# Sheet1.net
KiCad netlist of a schematic drawn in Altium Designer
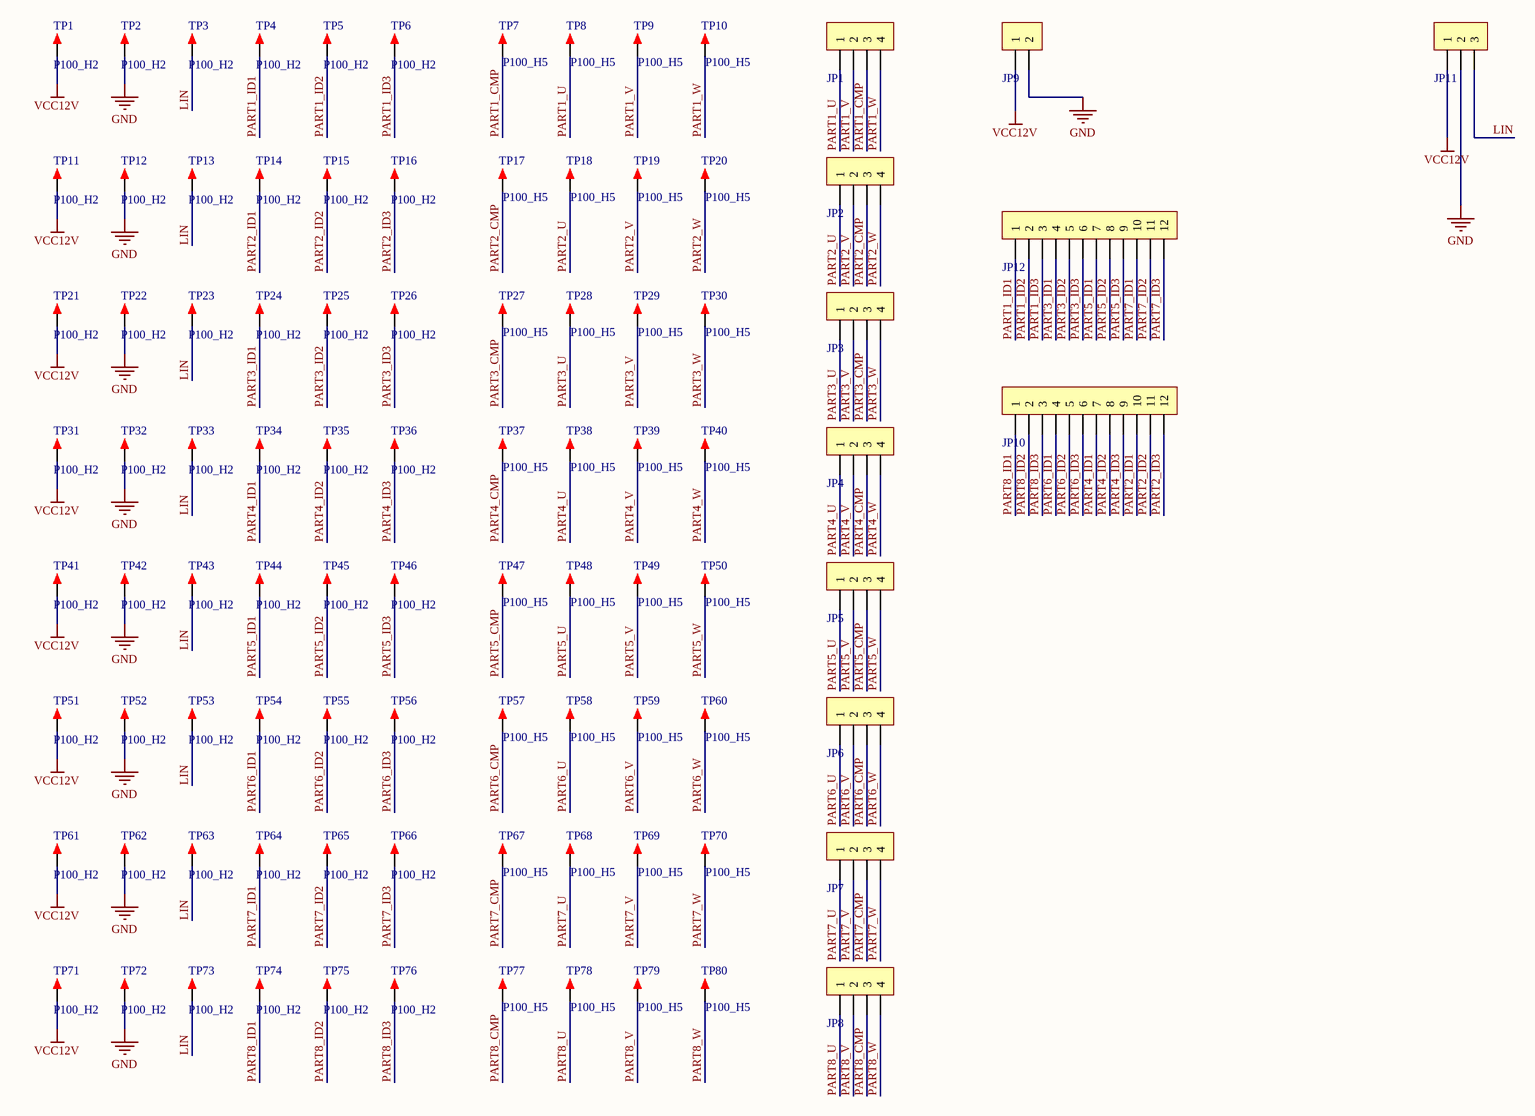
[diagram p0: Sheet1.SchDoc]

(export (version "E")
  (design (tool "Eeschema 10.0.6"))
  (components
    (comp (ref "JP1")
      (value "HDR-1X4")
      (footprint "XH2.54-LS-4P")
      (description "4P接插件")
      (fields (field (name "版权归属") "源创客"))
      (libsource (lib "Connector-PinHeader") (part "Header 4"))
    )
    (comp (ref "JP2")
      (value "HDR-1X4")
      (footprint "XH2.54-LS-4P")
      (description "4P接插件")
      (fields (field (name "版权归属") "源创客"))
      (libsource (lib "Connector-PinHeader") (part "Header 4"))
    )
    (comp (ref "JP3")
      (value "HDR-1X4")
      (footprint "XH2.54-LS-4P")
      (description "4P接插件")
      (fields (field (name "版权归属") "源创客"))
      (libsource (lib "Connector-PinHeader") (part "Header 4"))
    )
    (comp (ref "JP4")
      (value "HDR-1X4")
      (footprint "XH2.54-LS-4P")
      (description "4P接插件")
      (fields (field (name "版权归属") "源创客"))
      (libsource (lib "Connector-PinHeader") (part "Header 4"))
    )
    (comp (ref "JP5")
      (value "HDR-1X4")
      (footprint "XH2.54-LS-4P")
      (description "4P接插件")
      (fields (field (name "版权归属") "源创客"))
      (libsource (lib "Connector-PinHeader") (part "Header 4"))
    )
    (comp (ref "JP6")
      (value "HDR-1X4")
      (footprint "XH2.54-LS-4P")
      (description "4P接插件")
      (fields (field (name "版权归属") "源创客"))
      (libsource (lib "Connector-PinHeader") (part "Header 4"))
    )
    (comp (ref "JP7")
      (value "HDR-1X4")
      (footprint "XH2.54-LS-4P")
      (description "4P接插件")
      (fields (field (name "版权归属") "源创客"))
      (libsource (lib "Connector-PinHeader") (part "Header 4"))
    )
    (comp (ref "JP8")
      (value "HDR-1X4")
      (footprint "XH2.54-LS-4P")
      (description "4P接插件")
      (fields (field (name "版权归属") "源创客"))
      (libsource (lib "Connector-PinHeader") (part "Header 4"))
    )
    (comp (ref "JP9")
      (value "HDR-1X2")
      (footprint "DC-005P")
      (description "2P接插件")
      (fields (field (name "版权归属") "源创客"))
      (libsource (lib "Connector-PinHeader") (part "Header 2"))
    )
    (comp (ref "JP10")
      (value "HDR-1X12")
      (footprint "MX 1.25-WS-12P")
      (description "12P接插件")
      (fields (field (name "版权归属") "源创客"))
      (libsource (lib "Connector-PinHeader") (part "Header 12"))
    )
    (comp (ref "JP11")
      (value "HDR-1X3")
      (footprint "XH2.54-WS-3P")
      (description "3P接插件")
      (fields (field (name "版权归属") "源创客"))
      (libsource (lib "Connector-PinHeader") (part "Header 3"))
    )
    (comp (ref "JP12")
      (value "HDR-1X12")
      (footprint "MX 1.25-WS-12P")
      (description "12P接插件")
      (fields (field (name "版权归属") "源创客"))
      (libsource (lib "Connector-PinHeader") (part "Header 12"))
    )
    (comp (ref "TP1")
      (value "P100_H2")
      (footprint "P100_H2")
      (description "测试点")
      (fields (field (name "版权归属") "源创客"))
      (libsource (lib "Hole") (part "TEST"))
    )
    (comp (ref "TP2")
      (value "P100_H2")
      (footprint "P100_H2")
      (description "测试点")
      (fields (field (name "版权归属") "源创客"))
      (libsource (lib "Hole") (part "TEST"))
    )
    (comp (ref "TP3")
      (value "P100_H2")
      (footprint "P100_H2")
      (description "测试点")
      (fields (field (name "版权归属") "源创客"))
      (libsource (lib "Hole") (part "TEST"))
    )
    (comp (ref "TP4")
      (value "P100_H2")
      (footprint "P100_H2")
      (description "测试点")
      (fields (field (name "版权归属") "源创客"))
      (libsource (lib "Hole") (part "TEST"))
    )
    (comp (ref "TP5")
      (value "P100_H2")
      (footprint "P100_H2")
      (description "测试点")
      (fields (field (name "版权归属") "源创客"))
      (libsource (lib "Hole") (part "TEST"))
    )
    (comp (ref "TP6")
      (value "P100_H2")
      (footprint "P100_H2")
      (description "测试点")
      (fields (field (name "版权归属") "源创客"))
      (libsource (lib "Hole") (part "TEST"))
    )
    (comp (ref "TP7")
      (value "P100_H5")
      (footprint "P100_H5")
      (description "测试点")
      (fields (field (name "版权归属") "源创客"))
      (libsource (lib "Hole") (part "TEST"))
    )
    (comp (ref "TP8")
      (value "P100_H5")
      (footprint "P100_H5")
      (description "测试点")
      (fields (field (name "版权归属") "源创客"))
      (libsource (lib "Hole") (part "TEST"))
    )
    (comp (ref "TP9")
      (value "P100_H5")
      (footprint "P100_H5")
      (description "测试点")
      (fields (field (name "版权归属") "源创客"))
      (libsource (lib "Hole") (part "TEST"))
    )
    (comp (ref "TP10")
      (value "P100_H5")
      (footprint "P100_H5")
      (description "测试点")
      (fields (field (name "版权归属") "源创客"))
      (libsource (lib "Hole") (part "TEST"))
    )
    (comp (ref "TP11")
      (value "P100_H2")
      (footprint "P100_H2")
      (description "测试点")
      (fields (field (name "版权归属") "源创客"))
      (libsource (lib "Hole") (part "TEST"))
    )
    (comp (ref "TP12")
      (value "P100_H2")
      (footprint "P100_H2")
      (description "测试点")
      (fields (field (name "版权归属") "源创客"))
      (libsource (lib "Hole") (part "TEST"))
    )
    (comp (ref "TP13")
      (value "P100_H2")
      (footprint "P100_H2")
      (description "测试点")
      (fields (field (name "版权归属") "源创客"))
      (libsource (lib "Hole") (part "TEST"))
    )
    (comp (ref "TP14")
      (value "P100_H2")
      (footprint "P100_H2")
      (description "测试点")
      (fields (field (name "版权归属") "源创客"))
      (libsource (lib "Hole") (part "TEST"))
    )
    (comp (ref "TP15")
      (value "P100_H2")
      (footprint "P100_H2")
      (description "测试点")
      (fields (field (name "版权归属") "源创客"))
      (libsource (lib "Hole") (part "TEST"))
    )
    (comp (ref "TP16")
      (value "P100_H2")
      (footprint "P100_H2")
      (description "测试点")
      (fields (field (name "版权归属") "源创客"))
      (libsource (lib "Hole") (part "TEST"))
    )
    (comp (ref "TP17")
      (value "P100_H5")
      (footprint "P100_H5")
      (description "测试点")
      (fields (field (name "版权归属") "源创客"))
      (libsource (lib "Hole") (part "TEST"))
    )
    (comp (ref "TP18")
      (value "P100_H5")
      (footprint "P100_H5")
      (description "测试点")
      (fields (field (name "版权归属") "源创客"))
      (libsource (lib "Hole") (part "TEST"))
    )
    (comp (ref "TP19")
      (value "P100_H5")
      (footprint "P100_H5")
      (description "测试点")
      (fields (field (name "版权归属") "源创客"))
      (libsource (lib "Hole") (part "TEST"))
    )
    (comp (ref "TP20")
      (value "P100_H5")
      (footprint "P100_H5")
      (description "测试点")
      (fields (field (name "版权归属") "源创客"))
      (libsource (lib "Hole") (part "TEST"))
    )
    (comp (ref "TP21")
      (value "P100_H2")
      (footprint "P100_H2")
      (description "测试点")
      (fields (field (name "版权归属") "源创客"))
      (libsource (lib "Hole") (part "TEST"))
    )
    (comp (ref "TP22")
      (value "P100_H2")
      (footprint "P100_H2")
      (description "测试点")
      (fields (field (name "版权归属") "源创客"))
      (libsource (lib "Hole") (part "TEST"))
    )
    (comp (ref "TP23")
      (value "P100_H2")
      (footprint "P100_H2")
      (description "测试点")
      (fields (field (name "版权归属") "源创客"))
      (libsource (lib "Hole") (part "TEST"))
    )
    (comp (ref "TP24")
      (value "P100_H2")
      (footprint "P100_H2")
      (description "测试点")
      (fields (field (name "版权归属") "源创客"))
      (libsource (lib "Hole") (part "TEST"))
    )
    (comp (ref "TP25")
      (value "P100_H2")
      (footprint "P100_H2")
      (description "测试点")
      (fields (field (name "版权归属") "源创客"))
      (libsource (lib "Hole") (part "TEST"))
    )
    (comp (ref "TP26")
      (value "P100_H2")
      (footprint "P100_H2")
      (description "测试点")
      (fields (field (name "版权归属") "源创客"))
      (libsource (lib "Hole") (part "TEST"))
    )
    (comp (ref "TP27")
      (value "P100_H5")
      (footprint "P100_H5")
      (description "测试点")
      (fields (field (name "版权归属") "源创客"))
      (libsource (lib "Hole") (part "TEST"))
    )
    (comp (ref "TP28")
      (value "P100_H5")
      (footprint "P100_H5")
      (description "测试点")
      (fields (field (name "版权归属") "源创客"))
      (libsource (lib "Hole") (part "TEST"))
    )
    (comp (ref "TP29")
      (value "P100_H5")
      (footprint "P100_H5")
      (description "测试点")
      (fields (field (name "版权归属") "源创客"))
      (libsource (lib "Hole") (part "TEST"))
    )
    (comp (ref "TP30")
      (value "P100_H5")
      (footprint "P100_H5")
      (description "测试点")
      (fields (field (name "版权归属") "源创客"))
      (libsource (lib "Hole") (part "TEST"))
    )
    (comp (ref "TP31")
      (value "P100_H2")
      (footprint "P100_H2")
      (description "测试点")
      (fields (field (name "版权归属") "源创客"))
      (libsource (lib "Hole") (part "TEST"))
    )
    (comp (ref "TP32")
      (value "P100_H2")
      (footprint "P100_H2")
      (description "测试点")
      (fields (field (name "版权归属") "源创客"))
      (libsource (lib "Hole") (part "TEST"))
    )
    (comp (ref "TP33")
      (value "P100_H2")
      (footprint "P100_H2")
      (description "测试点")
      (fields (field (name "版权归属") "源创客"))
      (libsource (lib "Hole") (part "TEST"))
    )
    (comp (ref "TP34")
      (value "P100_H2")
      (footprint "P100_H2")
      (description "测试点")
      (fields (field (name "版权归属") "源创客"))
      (libsource (lib "Hole") (part "TEST"))
    )
    (comp (ref "TP35")
      (value "P100_H2")
      (footprint "P100_H2")
      (description "测试点")
      (fields (field (name "版权归属") "源创客"))
      (libsource (lib "Hole") (part "TEST"))
    )
    (comp (ref "TP36")
      (value "P100_H2")
      (footprint "P100_H2")
      (description "测试点")
      (fields (field (name "版权归属") "源创客"))
      (libsource (lib "Hole") (part "TEST"))
    )
    (comp (ref "TP37")
      (value "P100_H5")
      (footprint "P100_H5")
      (description "测试点")
      (fields (field (name "版权归属") "源创客"))
      (libsource (lib "Hole") (part "TEST"))
    )
    (comp (ref "TP38")
      (value "P100_H5")
      (footprint "P100_H5")
      (description "测试点")
      (fields (field (name "版权归属") "源创客"))
      (libsource (lib "Hole") (part "TEST"))
    )
    (comp (ref "TP39")
      (value "P100_H5")
      (footprint "P100_H5")
      (description "测试点")
      (fields (field (name "版权归属") "源创客"))
      (libsource (lib "Hole") (part "TEST"))
    )
    (comp (ref "TP40")
      (value "P100_H5")
      (footprint "P100_H5")
      (description "测试点")
      (fields (field (name "版权归属") "源创客"))
      (libsource (lib "Hole") (part "TEST"))
    )
    (comp (ref "TP41")
      (value "P100_H2")
      (footprint "P100_H2")
      (description "测试点")
      (fields (field (name "版权归属") "源创客"))
      (libsource (lib "Hole") (part "TEST"))
    )
    (comp (ref "TP42")
      (value "P100_H2")
      (footprint "P100_H2")
      (description "测试点")
      (fields (field (name "版权归属") "源创客"))
      (libsource (lib "Hole") (part "TEST"))
    )
    (comp (ref "TP43")
      (value "P100_H2")
      (footprint "P100_H2")
      (description "测试点")
      (fields (field (name "版权归属") "源创客"))
      (libsource (lib "Hole") (part "TEST"))
    )
    (comp (ref "TP44")
      (value "P100_H2")
      (footprint "P100_H2")
      (description "测试点")
      (fields (field (name "版权归属") "源创客"))
      (libsource (lib "Hole") (part "TEST"))
    )
    (comp (ref "TP45")
      (value "P100_H2")
      (footprint "P100_H2")
      (description "测试点")
      (fields (field (name "版权归属") "源创客"))
      (libsource (lib "Hole") (part "TEST"))
    )
    (comp (ref "TP46")
      (value "P100_H2")
      (footprint "P100_H2")
      (description "测试点")
      (fields (field (name "版权归属") "源创客"))
      (libsource (lib "Hole") (part "TEST"))
    )
    (comp (ref "TP47")
      (value "P100_H5")
      (footprint "P100_H5")
      (description "测试点")
      (fields (field (name "版权归属") "源创客"))
      (libsource (lib "Hole") (part "TEST"))
    )
    (comp (ref "TP48")
      (value "P100_H5")
      (footprint "P100_H5")
      (description "测试点")
      (fields (field (name "版权归属") "源创客"))
      (libsource (lib "Hole") (part "TEST"))
    )
    (comp (ref "TP49")
      (value "P100_H5")
      (footprint "P100_H5")
      (description "测试点")
      (fields (field (name "版权归属") "源创客"))
      (libsource (lib "Hole") (part "TEST"))
    )
    (comp (ref "TP50")
      (value "P100_H5")
      (footprint "P100_H5")
      (description "测试点")
      (fields (field (name "版权归属") "源创客"))
      (libsource (lib "Hole") (part "TEST"))
    )
    (comp (ref "TP51")
      (value "P100_H2")
      (footprint "P100_H2")
      (description "测试点")
      (fields (field (name "版权归属") "源创客"))
      (libsource (lib "Hole") (part "TEST"))
    )
    (comp (ref "TP52")
      (value "P100_H2")
      (footprint "P100_H2")
      (description "测试点")
      (fields (field (name "版权归属") "源创客"))
      (libsource (lib "Hole") (part "TEST"))
    )
    (comp (ref "TP53")
      (value "P100_H2")
      (footprint "P100_H2")
      (description "测试点")
      (fields (field (name "版权归属") "源创客"))
      (libsource (lib "Hole") (part "TEST"))
    )
    (comp (ref "TP54")
      (value "P100_H2")
      (footprint "P100_H2")
      (description "测试点")
      (fields (field (name "版权归属") "源创客"))
      (libsource (lib "Hole") (part "TEST"))
    )
    (comp (ref "TP55")
      (value "P100_H2")
      (footprint "P100_H2")
      (description "测试点")
      (fields (field (name "版权归属") "源创客"))
      (libsource (lib "Hole") (part "TEST"))
    )
    (comp (ref "TP56")
      (value "P100_H2")
      (footprint "P100_H2")
      (description "测试点")
      (fields (field (name "版权归属") "源创客"))
      (libsource (lib "Hole") (part "TEST"))
    )
    (comp (ref "TP57")
      (value "P100_H5")
      (footprint "P100_H5")
      (description "测试点")
      (fields (field (name "版权归属") "源创客"))
      (libsource (lib "Hole") (part "TEST"))
    )
    (comp (ref "TP58")
      (value "P100_H5")
      (footprint "P100_H5")
      (description "测试点")
      (fields (field (name "版权归属") "源创客"))
      (libsource (lib "Hole") (part "TEST"))
    )
    (comp (ref "TP59")
      (value "P100_H5")
      (footprint "P100_H5")
      (description "测试点")
      (fields (field (name "版权归属") "源创客"))
      (libsource (lib "Hole") (part "TEST"))
    )
    (comp (ref "TP60")
      (value "P100_H5")
      (footprint "P100_H5")
      (description "测试点")
      (fields (field (name "版权归属") "源创客"))
      (libsource (lib "Hole") (part "TEST"))
    )
    (comp (ref "TP61")
      (value "P100_H2")
      (footprint "P100_H2")
      (description "测试点")
      (fields (field (name "版权归属") "源创客"))
      (libsource (lib "Hole") (part "TEST"))
    )
    (comp (ref "TP62")
      (value "P100_H2")
      (footprint "P100_H2")
      (description "测试点")
      (fields (field (name "版权归属") "源创客"))
      (libsource (lib "Hole") (part "TEST"))
    )
    (comp (ref "TP63")
      (value "P100_H2")
      (footprint "P100_H2")
      (description "测试点")
      (fields (field (name "版权归属") "源创客"))
      (libsource (lib "Hole") (part "TEST"))
    )
    (comp (ref "TP64")
      (value "P100_H2")
      (footprint "P100_H2")
      (description "测试点")
      (fields (field (name "版权归属") "源创客"))
      (libsource (lib "Hole") (part "TEST"))
    )
    (comp (ref "TP65")
      (value "P100_H2")
      (footprint "P100_H2")
      (description "测试点")
      (fields (field (name "版权归属") "源创客"))
      (libsource (lib "Hole") (part "TEST"))
    )
    (comp (ref "TP66")
      (value "P100_H2")
      (footprint "P100_H2")
      (description "测试点")
      (fields (field (name "版权归属") "源创客"))
      (libsource (lib "Hole") (part "TEST"))
    )
    (comp (ref "TP67")
      (value "P100_H5")
      (footprint "P100_H5")
      (description "测试点")
      (fields (field (name "版权归属") "源创客"))
      (libsource (lib "Hole") (part "TEST"))
    )
    (comp (ref "TP68")
      (value "P100_H5")
      (footprint "P100_H5")
      (description "测试点")
      (fields (field (name "版权归属") "源创客"))
      (libsource (lib "Hole") (part "TEST"))
    )
    (comp (ref "TP69")
      (value "P100_H5")
      (footprint "P100_H5")
      (description "测试点")
      (fields (field (name "版权归属") "源创客"))
      (libsource (lib "Hole") (part "TEST"))
    )
    (comp (ref "TP70")
      (value "P100_H5")
      (footprint "P100_H5")
      (description "测试点")
      (fields (field (name "版权归属") "源创客"))
      (libsource (lib "Hole") (part "TEST"))
    )
    (comp (ref "TP71")
      (value "P100_H2")
      (footprint "P100_H2")
      (description "测试点")
      (fields (field (name "版权归属") "源创客"))
      (libsource (lib "Hole") (part "TEST"))
    )
    (comp (ref "TP72")
      (value "P100_H2")
      (footprint "P100_H2")
      (description "测试点")
      (fields (field (name "版权归属") "源创客"))
      (libsource (lib "Hole") (part "TEST"))
    )
    (comp (ref "TP73")
      (value "P100_H2")
      (footprint "P100_H2")
      (description "测试点")
      (fields (field (name "版权归属") "源创客"))
      (libsource (lib "Hole") (part "TEST"))
    )
    (comp (ref "TP74")
      (value "P100_H2")
      (footprint "P100_H2")
      (description "测试点")
      (fields (field (name "版权归属") "源创客"))
      (libsource (lib "Hole") (part "TEST"))
    )
    (comp (ref "TP75")
      (value "P100_H2")
      (footprint "P100_H2")
      (description "测试点")
      (fields (field (name "版权归属") "源创客"))
      (libsource (lib "Hole") (part "TEST"))
    )
    (comp (ref "TP76")
      (value "P100_H2")
      (footprint "P100_H2")
      (description "测试点")
      (fields (field (name "版权归属") "源创客"))
      (libsource (lib "Hole") (part "TEST"))
    )
    (comp (ref "TP77")
      (value "P100_H5")
      (footprint "P100_H5")
      (description "测试点")
      (fields (field (name "版权归属") "源创客"))
      (libsource (lib "Hole") (part "TEST"))
    )
    (comp (ref "TP78")
      (value "P100_H5")
      (footprint "P100_H5")
      (description "测试点")
      (fields (field (name "版权归属") "源创客"))
      (libsource (lib "Hole") (part "TEST"))
    )
    (comp (ref "TP79")
      (value "P100_H5")
      (footprint "P100_H5")
      (description "测试点")
      (fields (field (name "版权归属") "源创客"))
      (libsource (lib "Hole") (part "TEST"))
    )
    (comp (ref "TP80")
      (value "P100_H5")
      (footprint "P100_H5")
      (description "测试点")
      (fields (field (name "版权归属") "源创客"))
      (libsource (lib "Hole") (part "TEST"))
    )
  )
  (nets
    (net (code "1") (name "/LIN") (class "Default")
      (node (ref "JP11") (pin "3") (pinfunction "3_3") (pintype "passive"))
      (node (ref "TP13") (pin "1") (pinfunction "1_1") (pintype "passive"))
      (node (ref "TP23") (pin "1") (pinfunction "1_1") (pintype "passive"))
      (node (ref "TP3") (pin "1") (pinfunction "1_1") (pintype "passive"))
      (node (ref "TP33") (pin "1") (pinfunction "1_1") (pintype "passive"))
      (node (ref "TP43") (pin "1") (pinfunction "1_1") (pintype "passive"))
      (node (ref "TP53") (pin "1") (pinfunction "1_1") (pintype "passive"))
      (node (ref "TP63") (pin "1") (pinfunction "1_1") (pintype "passive"))
      (node (ref "TP73") (pin "1") (pinfunction "1_1") (pintype "passive"))
    )
    (net (code "2") (name "/PART1_CMP") (class "Default")
      (node (ref "JP1") (pin "3") (pinfunction "3_3") (pintype "passive"))
      (node (ref "TP7") (pin "1") (pinfunction "1_1") (pintype "passive"))
    )
    (net (code "3") (name "/PART1_ID1") (class "Default")
      (node (ref "JP12") (pin "1") (pinfunction "1_1") (pintype "passive"))
      (node (ref "TP4") (pin "1") (pinfunction "1_1") (pintype "passive"))
    )
    (net (code "4") (name "/PART1_ID2") (class "Default")
      (node (ref "JP12") (pin "2") (pinfunction "2_2") (pintype "passive"))
      (node (ref "TP5") (pin "1") (pinfunction "1_1") (pintype "passive"))
    )
    (net (code "5") (name "/PART1_ID3") (class "Default")
      (node (ref "JP12") (pin "3") (pinfunction "3_3") (pintype "passive"))
      (node (ref "TP6") (pin "1") (pinfunction "1_1") (pintype "passive"))
    )
    (net (code "6") (name "/PART1_U") (class "Default")
      (node (ref "JP1") (pin "1") (pinfunction "1_1") (pintype "passive"))
      (node (ref "TP8") (pin "1") (pinfunction "1_1") (pintype "passive"))
    )
    (net (code "7") (name "/PART1_V") (class "Default")
      (node (ref "JP1") (pin "2") (pinfunction "2_2") (pintype "passive"))
      (node (ref "TP9") (pin "1") (pinfunction "1_1") (pintype "passive"))
    )
    (net (code "8") (name "/PART1_W") (class "Default")
      (node (ref "JP1") (pin "4") (pinfunction "4_4") (pintype "passive"))
      (node (ref "TP10") (pin "1") (pinfunction "1_1") (pintype "passive"))
    )
    (net (code "9") (name "/PART2_CMP") (class "Default")
      (node (ref "JP2") (pin "3") (pinfunction "3_3") (pintype "passive"))
      (node (ref "TP17") (pin "1") (pinfunction "1_1") (pintype "passive"))
    )
    (net (code "10") (name "/PART2_ID1") (class "Default")
      (node (ref "JP10") (pin "10") (pinfunction "10_10") (pintype "passive"))
      (node (ref "TP14") (pin "1") (pinfunction "1_1") (pintype "passive"))
    )
    (net (code "11") (name "/PART2_ID2") (class "Default")
      (node (ref "JP10") (pin "11") (pinfunction "11_11") (pintype "passive"))
      (node (ref "TP15") (pin "1") (pinfunction "1_1") (pintype "passive"))
    )
    (net (code "12") (name "/PART2_ID3") (class "Default")
      (node (ref "JP10") (pin "12") (pinfunction "12_12") (pintype "passive"))
      (node (ref "TP16") (pin "1") (pinfunction "1_1") (pintype "passive"))
    )
    (net (code "13") (name "/PART2_U") (class "Default")
      (node (ref "JP2") (pin "1") (pinfunction "1_1") (pintype "passive"))
      (node (ref "TP18") (pin "1") (pinfunction "1_1") (pintype "passive"))
    )
    (net (code "14") (name "/PART2_V") (class "Default")
      (node (ref "JP2") (pin "2") (pinfunction "2_2") (pintype "passive"))
      (node (ref "TP19") (pin "1") (pinfunction "1_1") (pintype "passive"))
    )
    (net (code "15") (name "/PART2_W") (class "Default")
      (node (ref "JP2") (pin "4") (pinfunction "4_4") (pintype "passive"))
      (node (ref "TP20") (pin "1") (pinfunction "1_1") (pintype "passive"))
    )
    (net (code "16") (name "/PART3_CMP") (class "Default")
      (node (ref "JP3") (pin "3") (pinfunction "3_3") (pintype "passive"))
      (node (ref "TP27") (pin "1") (pinfunction "1_1") (pintype "passive"))
    )
    (net (code "17") (name "/PART3_ID1") (class "Default")
      (node (ref "JP12") (pin "4") (pinfunction "4_4") (pintype "passive"))
      (node (ref "TP24") (pin "1") (pinfunction "1_1") (pintype "passive"))
    )
    (net (code "18") (name "/PART3_ID2") (class "Default")
      (node (ref "JP12") (pin "5") (pinfunction "5_5") (pintype "passive"))
      (node (ref "TP25") (pin "1") (pinfunction "1_1") (pintype "passive"))
    )
    (net (code "19") (name "/PART3_ID3") (class "Default")
      (node (ref "JP12") (pin "6") (pinfunction "6_6") (pintype "passive"))
      (node (ref "TP26") (pin "1") (pinfunction "1_1") (pintype "passive"))
    )
    (net (code "20") (name "/PART3_U") (class "Default")
      (node (ref "JP3") (pin "1") (pinfunction "1_1") (pintype "passive"))
      (node (ref "TP28") (pin "1") (pinfunction "1_1") (pintype "passive"))
    )
    (net (code "21") (name "/PART3_V") (class "Default")
      (node (ref "JP3") (pin "2") (pinfunction "2_2") (pintype "passive"))
      (node (ref "TP29") (pin "1") (pinfunction "1_1") (pintype "passive"))
    )
    (net (code "22") (name "/PART3_W") (class "Default")
      (node (ref "JP3") (pin "4") (pinfunction "4_4") (pintype "passive"))
      (node (ref "TP30") (pin "1") (pinfunction "1_1") (pintype "passive"))
    )
    (net (code "23") (name "/PART4_CMP") (class "Default")
      (node (ref "JP4") (pin "3") (pinfunction "3_3") (pintype "passive"))
      (node (ref "TP37") (pin "1") (pinfunction "1_1") (pintype "passive"))
    )
    (net (code "24") (name "/PART4_ID1") (class "Default")
      (node (ref "JP10") (pin "7") (pinfunction "7_7") (pintype "passive"))
      (node (ref "TP34") (pin "1") (pinfunction "1_1") (pintype "passive"))
    )
    (net (code "25") (name "/PART4_ID2") (class "Default")
      (node (ref "JP10") (pin "8") (pinfunction "8_8") (pintype "passive"))
      (node (ref "TP35") (pin "1") (pinfunction "1_1") (pintype "passive"))
    )
    (net (code "26") (name "/PART4_ID3") (class "Default")
      (node (ref "JP10") (pin "9") (pinfunction "9_9") (pintype "passive"))
      (node (ref "TP36") (pin "1") (pinfunction "1_1") (pintype "passive"))
    )
    (net (code "27") (name "/PART4_U") (class "Default")
      (node (ref "JP4") (pin "1") (pinfunction "1_1") (pintype "passive"))
      (node (ref "TP38") (pin "1") (pinfunction "1_1") (pintype "passive"))
    )
    (net (code "28") (name "/PART4_V") (class "Default")
      (node (ref "JP4") (pin "2") (pinfunction "2_2") (pintype "passive"))
      (node (ref "TP39") (pin "1") (pinfunction "1_1") (pintype "passive"))
    )
    (net (code "29") (name "/PART4_W") (class "Default")
      (node (ref "JP4") (pin "4") (pinfunction "4_4") (pintype "passive"))
      (node (ref "TP40") (pin "1") (pinfunction "1_1") (pintype "passive"))
    )
    (net (code "30") (name "/PART5_CMP") (class "Default")
      (node (ref "JP5") (pin "3") (pinfunction "3_3") (pintype "passive"))
      (node (ref "TP47") (pin "1") (pinfunction "1_1") (pintype "passive"))
    )
    (net (code "31") (name "/PART5_ID1") (class "Default")
      (node (ref "JP12") (pin "7") (pinfunction "7_7") (pintype "passive"))
      (node (ref "TP44") (pin "1") (pinfunction "1_1") (pintype "passive"))
    )
    (net (code "32") (name "/PART5_ID2") (class "Default")
      (node (ref "JP12") (pin "8") (pinfunction "8_8") (pintype "passive"))
      (node (ref "TP45") (pin "1") (pinfunction "1_1") (pintype "passive"))
    )
    (net (code "33") (name "/PART5_ID3") (class "Default")
      (node (ref "JP12") (pin "9") (pinfunction "9_9") (pintype "passive"))
      (node (ref "TP46") (pin "1") (pinfunction "1_1") (pintype "passive"))
    )
    (net (code "34") (name "/PART5_U") (class "Default")
      (node (ref "JP5") (pin "1") (pinfunction "1_1") (pintype "passive"))
      (node (ref "TP48") (pin "1") (pinfunction "1_1") (pintype "passive"))
    )
    (net (code "35") (name "/PART5_V") (class "Default")
      (node (ref "JP5") (pin "2") (pinfunction "2_2") (pintype "passive"))
      (node (ref "TP49") (pin "1") (pinfunction "1_1") (pintype "passive"))
    )
    (net (code "36") (name "/PART5_W") (class "Default")
      (node (ref "JP5") (pin "4") (pinfunction "4_4") (pintype "passive"))
      (node (ref "TP50") (pin "1") (pinfunction "1_1") (pintype "passive"))
    )
    (net (code "37") (name "/PART6_CMP") (class "Default")
      (node (ref "JP6") (pin "3") (pinfunction "3_3") (pintype "passive"))
      (node (ref "TP57") (pin "1") (pinfunction "1_1") (pintype "passive"))
    )
    (net (code "38") (name "/PART6_ID1") (class "Default")
      (node (ref "JP10") (pin "4") (pinfunction "4_4") (pintype "passive"))
      (node (ref "TP54") (pin "1") (pinfunction "1_1") (pintype "passive"))
    )
    (net (code "39") (name "/PART6_ID2") (class "Default")
      (node (ref "JP10") (pin "5") (pinfunction "5_5") (pintype "passive"))
      (node (ref "TP55") (pin "1") (pinfunction "1_1") (pintype "passive"))
    )
    (net (code "40") (name "/PART6_ID3") (class "Default")
      (node (ref "JP10") (pin "6") (pinfunction "6_6") (pintype "passive"))
      (node (ref "TP56") (pin "1") (pinfunction "1_1") (pintype "passive"))
    )
    (net (code "41") (name "/PART6_U") (class "Default")
      (node (ref "JP6") (pin "1") (pinfunction "1_1") (pintype "passive"))
      (node (ref "TP58") (pin "1") (pinfunction "1_1") (pintype "passive"))
    )
    (net (code "42") (name "/PART6_V") (class "Default")
      (node (ref "JP6") (pin "2") (pinfunction "2_2") (pintype "passive"))
      (node (ref "TP59") (pin "1") (pinfunction "1_1") (pintype "passive"))
    )
    (net (code "43") (name "/PART6_W") (class "Default")
      (node (ref "JP6") (pin "4") (pinfunction "4_4") (pintype "passive"))
      (node (ref "TP60") (pin "1") (pinfunction "1_1") (pintype "passive"))
    )
    (net (code "44") (name "/PART7_CMP") (class "Default")
      (node (ref "JP7") (pin "3") (pinfunction "3_3") (pintype "passive"))
      (node (ref "TP67") (pin "1") (pinfunction "1_1") (pintype "passive"))
    )
    (net (code "45") (name "/PART7_ID1") (class "Default")
      (node (ref "JP12") (pin "10") (pinfunction "10_10") (pintype "passive"))
      (node (ref "TP64") (pin "1") (pinfunction "1_1") (pintype "passive"))
    )
    (net (code "46") (name "/PART7_ID2") (class "Default")
      (node (ref "JP12") (pin "11") (pinfunction "11_11") (pintype "passive"))
      (node (ref "TP65") (pin "1") (pinfunction "1_1") (pintype "passive"))
    )
    (net (code "47") (name "/PART7_ID3") (class "Default")
      (node (ref "JP12") (pin "12") (pinfunction "12_12") (pintype "passive"))
      (node (ref "TP66") (pin "1") (pinfunction "1_1") (pintype "passive"))
    )
    (net (code "48") (name "/PART7_U") (class "Default")
      (node (ref "JP7") (pin "1") (pinfunction "1_1") (pintype "passive"))
      (node (ref "TP68") (pin "1") (pinfunction "1_1") (pintype "passive"))
    )
    (net (code "49") (name "/PART7_V") (class "Default")
      (node (ref "JP7") (pin "2") (pinfunction "2_2") (pintype "passive"))
      (node (ref "TP69") (pin "1") (pinfunction "1_1") (pintype "passive"))
    )
    (net (code "50") (name "/PART7_W") (class "Default")
      (node (ref "JP7") (pin "4") (pinfunction "4_4") (pintype "passive"))
      (node (ref "TP70") (pin "1") (pinfunction "1_1") (pintype "passive"))
    )
    (net (code "51") (name "/PART8_CMP") (class "Default")
      (node (ref "JP8") (pin "3") (pinfunction "3_3") (pintype "passive"))
      (node (ref "TP77") (pin "1") (pinfunction "1_1") (pintype "passive"))
    )
    (net (code "52") (name "/PART8_ID1") (class "Default")
      (node (ref "JP10") (pin "1") (pinfunction "1_1") (pintype "passive"))
      (node (ref "TP74") (pin "1") (pinfunction "1_1") (pintype "passive"))
    )
    (net (code "53") (name "/PART8_ID2") (class "Default")
      (node (ref "JP10") (pin "2") (pinfunction "2_2") (pintype "passive"))
      (node (ref "TP75") (pin "1") (pinfunction "1_1") (pintype "passive"))
    )
    (net (code "54") (name "/PART8_ID3") (class "Default")
      (node (ref "JP10") (pin "3") (pinfunction "3_3") (pintype "passive"))
      (node (ref "TP76") (pin "1") (pinfunction "1_1") (pintype "passive"))
    )
    (net (code "55") (name "/PART8_U") (class "Default")
      (node (ref "JP8") (pin "1") (pinfunction "1_1") (pintype "passive"))
      (node (ref "TP78") (pin "1") (pinfunction "1_1") (pintype "passive"))
    )
    (net (code "56") (name "/PART8_V") (class "Default")
      (node (ref "JP8") (pin "2") (pinfunction "2_2") (pintype "passive"))
      (node (ref "TP79") (pin "1") (pinfunction "1_1") (pintype "passive"))
    )
    (net (code "57") (name "/PART8_W") (class "Default")
      (node (ref "JP8") (pin "4") (pinfunction "4_4") (pintype "passive"))
      (node (ref "TP80") (pin "1") (pinfunction "1_1") (pintype "passive"))
    )
    (net (code "58") (name "GND") (class "Default")
      (node (ref "JP11") (pin "2") (pinfunction "2_2") (pintype "passive"))
      (node (ref "JP9") (pin "2") (pinfunction "2_2") (pintype "passive"))
      (node (ref "TP12") (pin "1") (pinfunction "1_1") (pintype "passive"))
      (node (ref "TP2") (pin "1") (pinfunction "1_1") (pintype "passive"))
      (node (ref "TP22") (pin "1") (pinfunction "1_1") (pintype "passive"))
      (node (ref "TP32") (pin "1") (pinfunction "1_1") (pintype "passive"))
      (node (ref "TP42") (pin "1") (pinfunction "1_1") (pintype "passive"))
      (node (ref "TP52") (pin "1") (pinfunction "1_1") (pintype "passive"))
      (node (ref "TP62") (pin "1") (pinfunction "1_1") (pintype "passive"))
      (node (ref "TP72") (pin "1") (pinfunction "1_1") (pintype "passive"))
    )
    (net (code "59") (name "VCC12V") (class "Default")
      (node (ref "JP11") (pin "1") (pinfunction "1_1") (pintype "passive"))
      (node (ref "JP9") (pin "1") (pinfunction "1_1") (pintype "passive"))
      (node (ref "TP1") (pin "1") (pinfunction "1_1") (pintype "passive"))
      (node (ref "TP11") (pin "1") (pinfunction "1_1") (pintype "passive"))
      (node (ref "TP21") (pin "1") (pinfunction "1_1") (pintype "passive"))
      (node (ref "TP31") (pin "1") (pinfunction "1_1") (pintype "passive"))
      (node (ref "TP41") (pin "1") (pinfunction "1_1") (pintype "passive"))
      (node (ref "TP51") (pin "1") (pinfunction "1_1") (pintype "passive"))
      (node (ref "TP61") (pin "1") (pinfunction "1_1") (pintype "passive"))
      (node (ref "TP71") (pin "1") (pinfunction "1_1") (pintype "passive"))
    )
  )
)
